# buttons.net
KiCad netlist of a schematic drawn in EAGLE
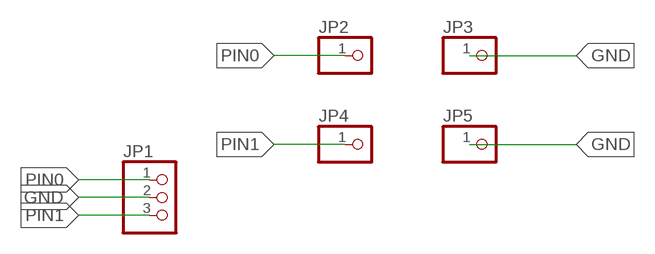
[diagram p0: schematic, sheet 1]

(export (version "E")
  (design (tool "Eeschema 10.0.6"))
  (components
    (comp (ref "JP1")
      (value "PINHD-1X3")
      (footprint "eagle-import:1X03")
      (libsource (lib "eagle-import") (part "PINHD-1X3"))
    )
    (comp (ref "JP2")
      (value "PINHD-1X1")
      (footprint "eagle-import:1X01")
      (libsource (lib "eagle-import") (part "PINHD-1X1"))
    )
    (comp (ref "JP3")
      (value "PINHD-1X1")
      (footprint "eagle-import:1X01")
      (libsource (lib "eagle-import") (part "PINHD-1X1"))
    )
    (comp (ref "JP4")
      (value "PINHD-1X1")
      (footprint "eagle-import:1X01")
      (libsource (lib "eagle-import") (part "PINHD-1X1"))
    )
    (comp (ref "JP5")
      (value "PINHD-1X1")
      (footprint "eagle-import:1X01")
      (libsource (lib "eagle-import") (part "PINHD-1X1"))
    )
  )
  (nets
    (net (code "1") (name "GND") (class "Default")
      (node (ref "JP1") (pin "2") (pinfunction "2_2") (pintype "passive"))
      (node (ref "JP3") (pin "1") (pinfunction "1_1") (pintype "passive"))
      (node (ref "JP5") (pin "1") (pinfunction "1_1") (pintype "passive"))
    )
    (net (code "2") (name "PIN0") (class "Default")
      (node (ref "JP1") (pin "1") (pinfunction "1_1") (pintype "passive"))
      (node (ref "JP2") (pin "1") (pinfunction "1_1") (pintype "passive"))
    )
    (net (code "3") (name "PIN1") (class "Default")
      (node (ref "JP1") (pin "3") (pinfunction "3_3") (pintype "passive"))
      (node (ref "JP4") (pin "1") (pinfunction "1_1") (pintype "passive"))
    )
  )
)
